# atx_power_control.net
KiCad netlist of a schematic drawn in EAGLE
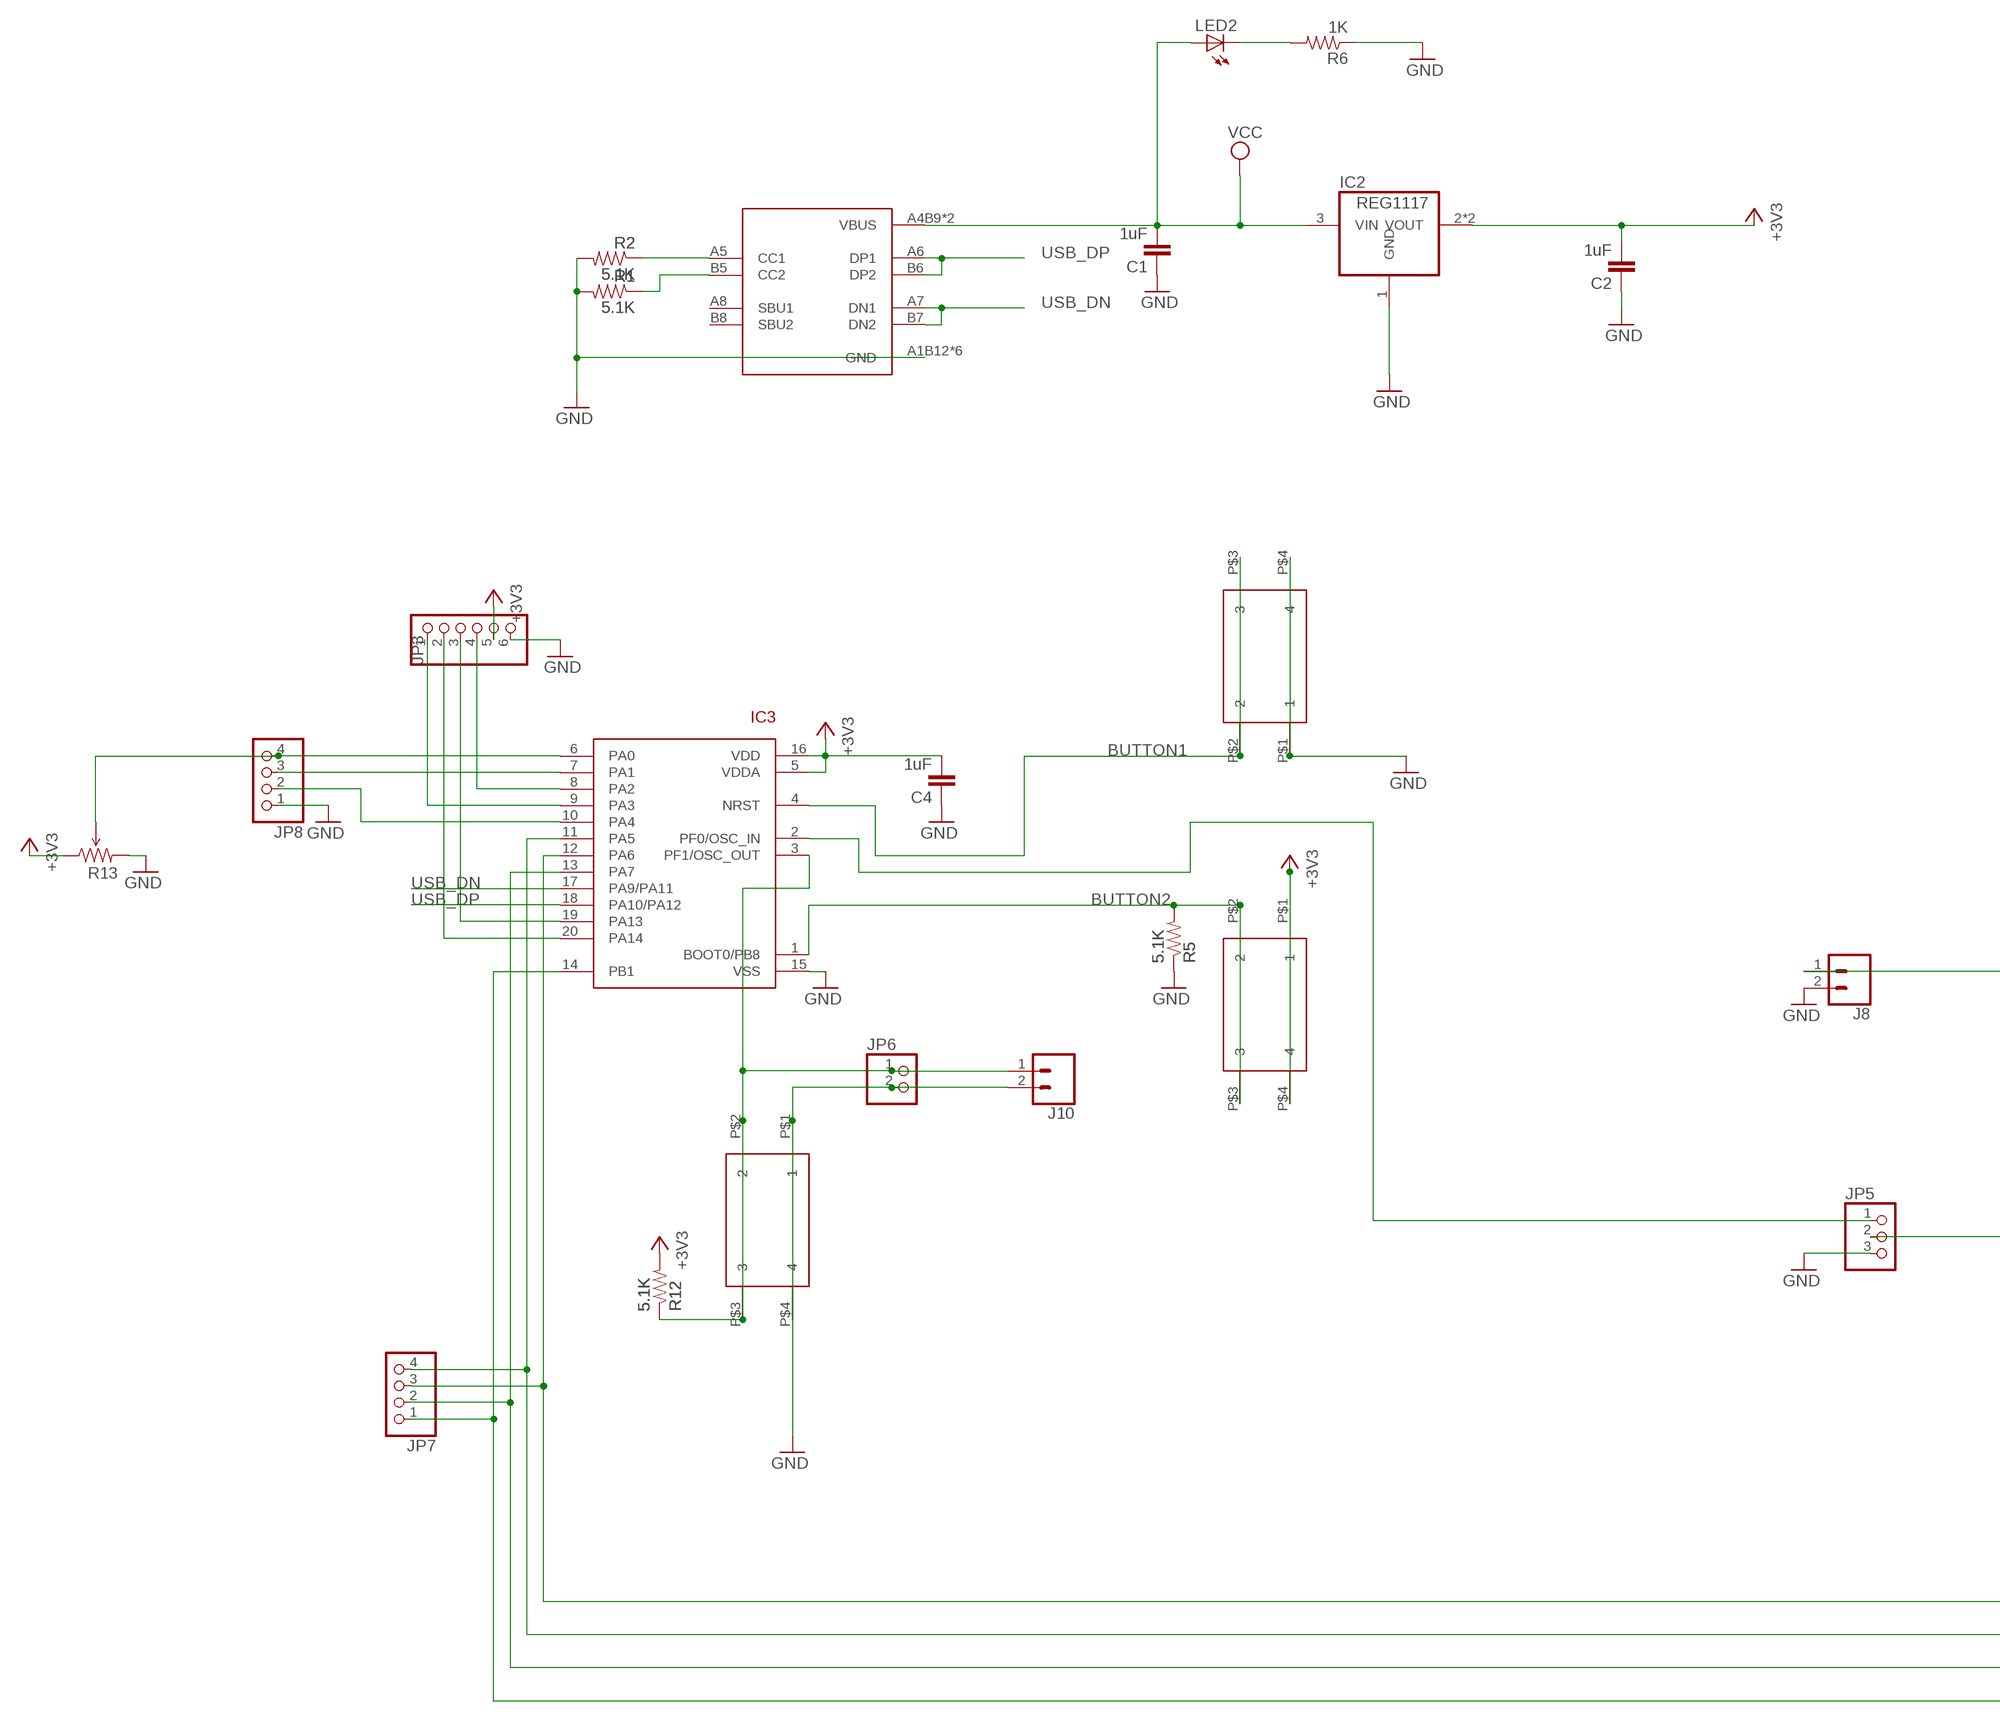
[diagram p0: schematic, sheet 1, part 1 of 2]
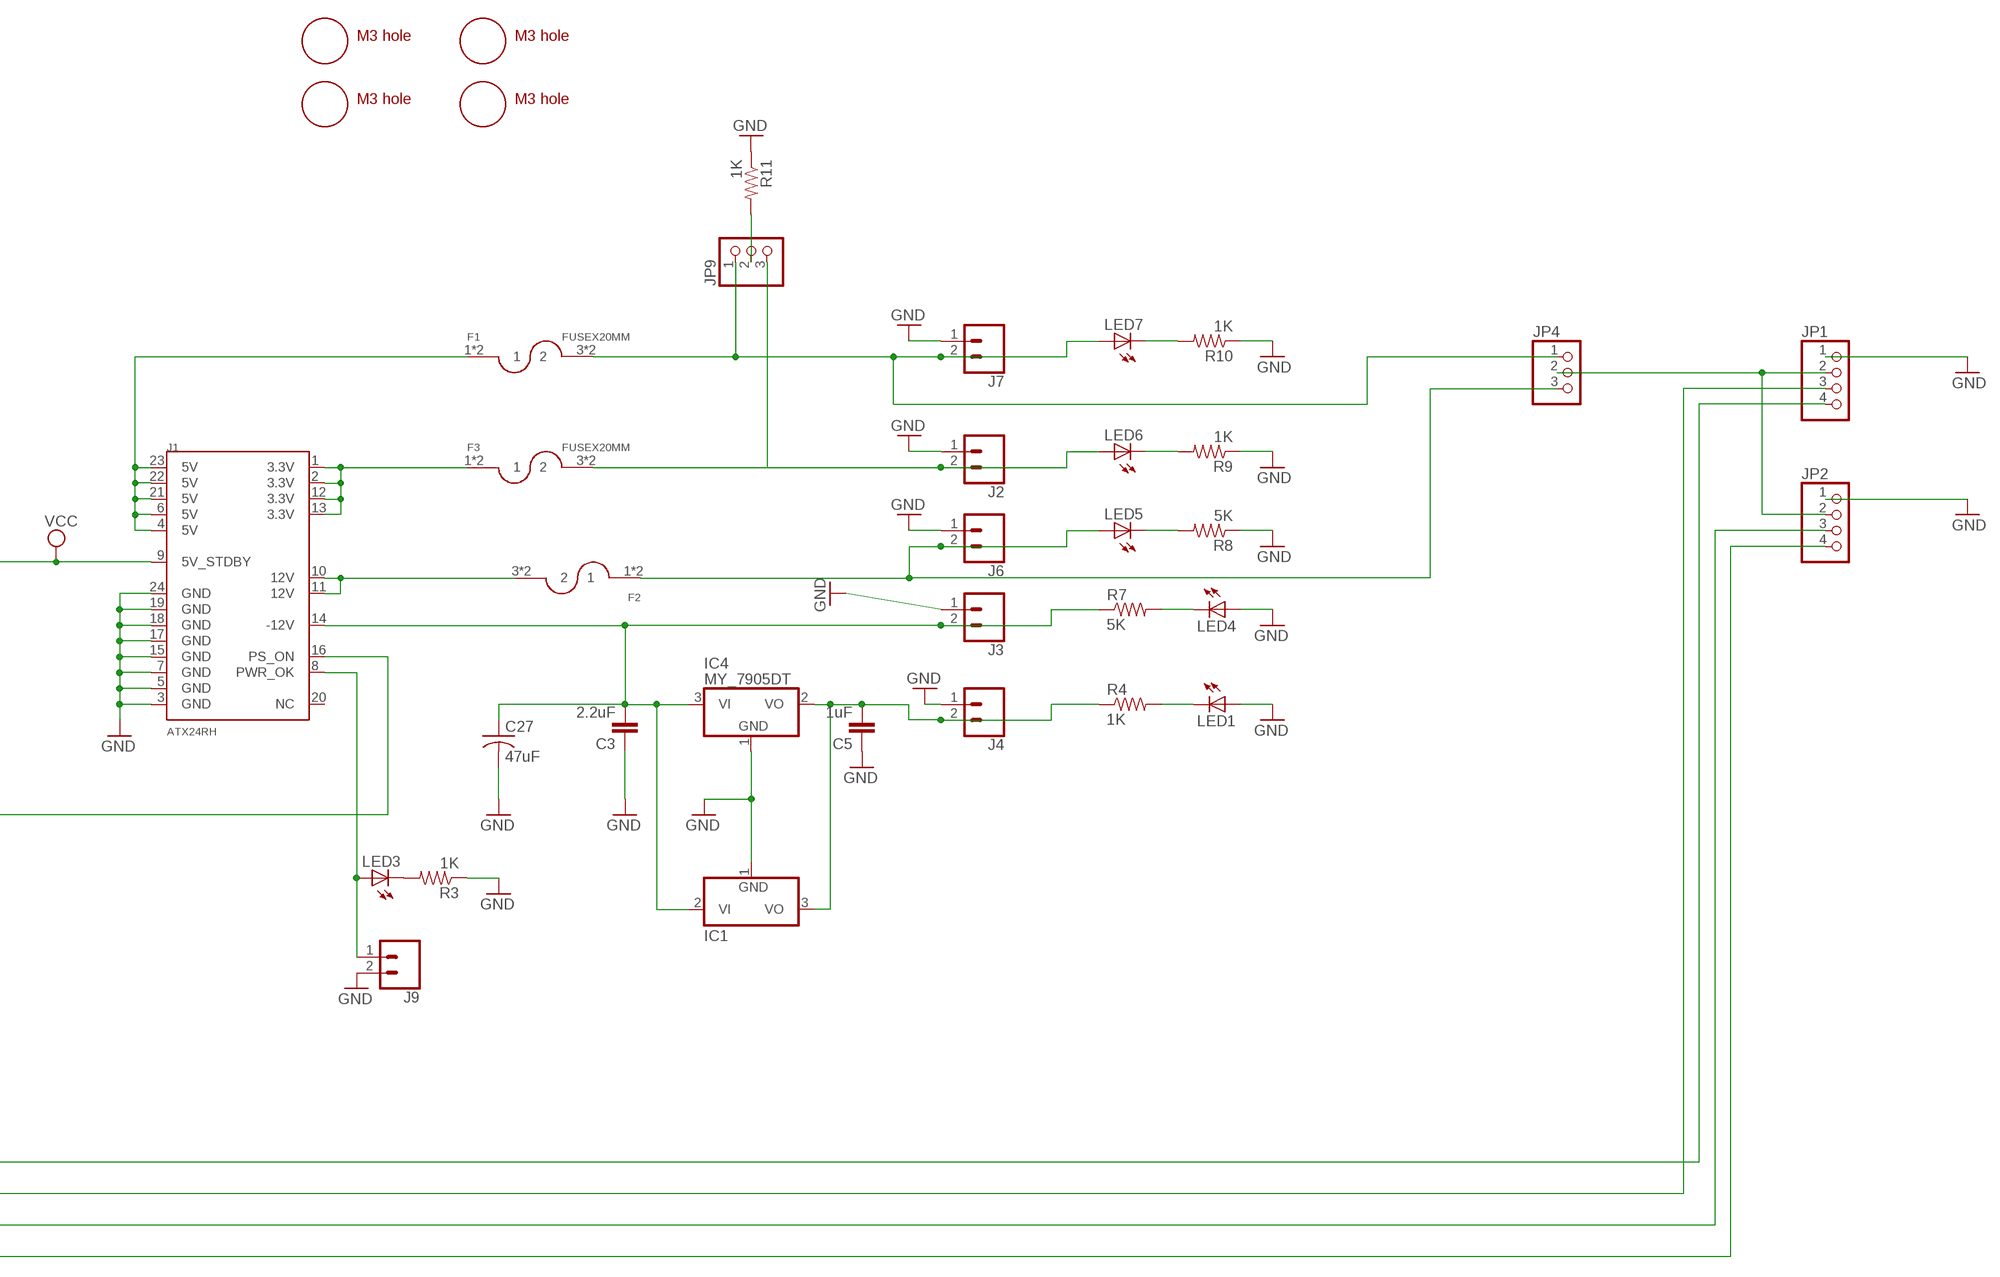
[diagram p1: schematic, sheet 1, part 2 of 2]

(export (version "E")
  (design (tool "Eeschema 10.0.6"))
  (components
    (comp (ref "C1")
      (value "1uF")
      (footprint "eagle-import:0805@1")
      (libsource (lib "eagle-import") (part "CAP0805"))
    )
    (comp (ref "C2")
      (value "1uF")
      (footprint "eagle-import:0805@1")
      (libsource (lib "eagle-import") (part "CAP0805"))
    )
    (comp (ref "C3")
      (value "2.2uF")
      (footprint "eagle-import:0805@1")
      (libsource (lib "eagle-import") (part "CAP0805"))
    )
    (comp (ref "C4")
      (value "1uF")
      (footprint "eagle-import:0805@1")
      (libsource (lib "eagle-import") (part "CAP0805"))
    )
    (comp (ref "C5")
      (value "1uF")
      (footprint "eagle-import:0805@1")
      (libsource (lib "eagle-import") (part "CAP0805"))
    )
    (comp (ref "C27")
      (value "47uF")
      (footprint "eagle-import:C1210")
      (libsource (lib "eagle-import") (part "C-USC1210"))
    )
    (comp (ref "F1")
      (value "FUSEX20MM")
      (footprint "eagle-import:FUSE_5MM")
      (libsource (lib "eagle-import") (part "FUSEX20MM"))
    )
    (comp (ref "F2")
      (value "FUSEX20MM")
      (footprint "eagle-import:FUSE_5MM")
      (libsource (lib "eagle-import") (part "FUSEX20MM"))
    )
    (comp (ref "F3")
      (value "FUSEX20MM")
      (footprint "eagle-import:FUSE_5MM")
      (libsource (lib "eagle-import") (part "FUSEX20MM"))
    )
    (comp (ref "IC1")
      (value "7905T")
      (footprint "eagle-import:TO220H")
      (libsource (lib "eagle-import") (part "79T05"))
    )
    (comp (ref "IC2")
      (value "REG1117")
      (footprint "eagle-import:SOT223")
      (libsource (lib "eagle-import") (part "REG1117"))
    )
    (comp (ref "IC3")
      (value "STM32F042F4")
      (footprint "eagle-import:TSSOP20")
      (libsource (lib "eagle-import") (part "STM32F042F4"))
    )
    (comp (ref "IC4")
      (value "MY_7905DT")
      (footprint "eagle-import:ADAFRUIT_TO252")
      (libsource (lib "eagle-import") (part "MY_7905DT"))
    )
    (comp (ref "J1")
      (value "ATX24RH")
      (footprint "eagle-import:ATX24_RIGHT_ANGLE")
      (libsource (lib "eagle-import") (part "ATX24RH"))
    )
    (comp (ref "J2")
      (value "CONN_023.5MM")
      (footprint "eagle-import:SCREWTERMINAL-3.5MM-2")
      (libsource (lib "eagle-import") (part "CONN_023.5MM"))
    )
    (comp (ref "J3")
      (value "CONN_023.5MM")
      (footprint "eagle-import:SCREWTERMINAL-3.5MM-2")
      (libsource (lib "eagle-import") (part "CONN_023.5MM"))
    )
    (comp (ref "J4")
      (value "CONN_023.5MM")
      (footprint "eagle-import:SCREWTERMINAL-3.5MM-2")
      (libsource (lib "eagle-import") (part "CONN_023.5MM"))
    )
    (comp (ref "J6")
      (value "CONN_023.5MM")
      (footprint "eagle-import:SCREWTERMINAL-3.5MM-2")
      (libsource (lib "eagle-import") (part "CONN_023.5MM"))
    )
    (comp (ref "J7")
      (value "CONN_023.5MM")
      (footprint "eagle-import:SCREWTERMINAL-3.5MM-2")
      (libsource (lib "eagle-import") (part "CONN_023.5MM"))
    )
    (comp (ref "J8")
      (value "CONN_023.5MM")
      (footprint "eagle-import:SCREWTERMINAL-3.5MM-2")
      (libsource (lib "eagle-import") (part "CONN_023.5MM"))
    )
    (comp (ref "J9")
      (value "CONN_023.5MM")
      (footprint "eagle-import:SCREWTERMINAL-3.5MM-2")
      (libsource (lib "eagle-import") (part "CONN_023.5MM"))
    )
    (comp (ref "J10")
      (value "CONN_023.5MM")
      (footprint "eagle-import:SCREWTERMINAL-3.5MM-2")
      (libsource (lib "eagle-import") (part "CONN_023.5MM"))
    )
    (comp (ref "JP1")
      (value "PINHD-1X4")
      (footprint "eagle-import:1X04")
      (libsource (lib "eagle-import") (part "PINHD-1X4"))
    )
    (comp (ref "JP2")
      (value "PINHD-1X4")
      (footprint "eagle-import:1X04")
      (libsource (lib "eagle-import") (part "PINHD-1X4"))
    )
    (comp (ref "JP3")
      (value "PINHD-1X6")
      (footprint "eagle-import:1X06")
      (libsource (lib "eagle-import") (part "PINHD-1X6"))
    )
    (comp (ref "JP4")
      (value "PINHD-1X3")
      (footprint "eagle-import:1X03")
      (libsource (lib "eagle-import") (part "PINHD-1X3"))
    )
    (comp (ref "JP5")
      (value "PINHD-1X3")
      (footprint "eagle-import:1X03")
      (libsource (lib "eagle-import") (part "PINHD-1X3"))
    )
    (comp (ref "JP6")
      (value "PINHD-1X2")
      (footprint "eagle-import:1X02")
      (libsource (lib "eagle-import") (part "PINHD-1X2"))
    )
    (comp (ref "JP7")
      (value "PINHD-1X4")
      (footprint "eagle-import:1X04")
      (libsource (lib "eagle-import") (part "PINHD-1X4"))
    )
    (comp (ref "JP8")
      (value "PINHD-1X4")
      (footprint "eagle-import:1X04")
      (libsource (lib "eagle-import") (part "PINHD-1X4"))
    )
    (comp (ref "JP9")
      (value "PINHD-1X3")
      (footprint "eagle-import:1X03")
      (libsource (lib "eagle-import") (part "PINHD-1X3"))
    )
    (comp (ref "LED1")
      (value "LEDCHIP-LED0805")
      (footprint "eagle-import:CHIP-LED0805")
      (libsource (lib "eagle-import") (part "LEDCHIP-LED0805"))
    )
    (comp (ref "LED2")
      (value "LEDCHIP-LED0805")
      (footprint "eagle-import:CHIP-LED0805")
      (libsource (lib "eagle-import") (part "LEDCHIP-LED0805"))
    )
    (comp (ref "LED3")
      (value "LEDCHIP-LED0805")
      (footprint "eagle-import:CHIP-LED0805")
      (libsource (lib "eagle-import") (part "LEDCHIP-LED0805"))
    )
    (comp (ref "LED4")
      (value "LEDCHIP-LED0805")
      (footprint "eagle-import:CHIP-LED0805")
      (libsource (lib "eagle-import") (part "LEDCHIP-LED0805"))
    )
    (comp (ref "LED5")
      (value "LEDCHIP-LED0805")
      (footprint "eagle-import:CHIP-LED0805")
      (libsource (lib "eagle-import") (part "LEDCHIP-LED0805"))
    )
    (comp (ref "LED6")
      (value "LEDCHIP-LED0805")
      (footprint "eagle-import:CHIP-LED0805")
      (libsource (lib "eagle-import") (part "LEDCHIP-LED0805"))
    )
    (comp (ref "LED7")
      (value "LEDCHIP-LED0805")
      (footprint "eagle-import:CHIP-LED0805")
      (libsource (lib "eagle-import") (part "LEDCHIP-LED0805"))
    )
    (comp (ref "R1")
      (value "5.1K")
      (footprint "eagle-import:0805")
      (libsource (lib "eagle-import") (part "joyAnalog_RESISTOR0805-RES"))
    )
    (comp (ref "R2")
      (value "5.1K")
      (footprint "eagle-import:0805")
      (libsource (lib "eagle-import") (part "joyAnalog_RESISTOR0805-RES"))
    )
    (comp (ref "R3")
      (value "1K")
      (footprint "eagle-import:0805")
      (libsource (lib "eagle-import") (part "RESISTOR0805-RES"))
    )
    (comp (ref "R4")
      (value "1K")
      (footprint "eagle-import:0805")
      (libsource (lib "eagle-import") (part "RESISTOR0805-RES"))
    )
    (comp (ref "R5")
      (value "5.1K")
      (footprint "eagle-import:0805")
      (libsource (lib "eagle-import") (part "joyAnalog_RESISTOR0805-RES"))
    )
    (comp (ref "R6")
      (value "1K")
      (footprint "eagle-import:0805")
      (libsource (lib "eagle-import") (part "RESISTOR0805-RES"))
    )
    (comp (ref "R7")
      (value "5K")
      (footprint "eagle-import:0805")
      (libsource (lib "eagle-import") (part "RESISTOR0805-RES"))
    )
    (comp (ref "R8")
      (value "5K")
      (footprint "eagle-import:0805")
      (libsource (lib "eagle-import") (part "RESISTOR0805-RES"))
    )
    (comp (ref "R9")
      (value "1K")
      (footprint "eagle-import:0805")
      (libsource (lib "eagle-import") (part "RESISTOR0805-RES"))
    )
    (comp (ref "R10")
      (value "1K")
      (footprint "eagle-import:0805")
      (libsource (lib "eagle-import") (part "RESISTOR0805-RES"))
    )
    (comp (ref "R11")
      (value "1K")
      (footprint "eagle-import:0805")
      (libsource (lib "eagle-import") (part "RESISTOR0805-RES"))
    )
    (comp (ref "R12")
      (value "5.1K")
      (footprint "eagle-import:0805")
      (libsource (lib "eagle-import") (part "joyAnalog_RESISTOR0805-RES"))
    )
    (comp (ref "R13")
      (value "TRIMPOTPTH")
      (footprint "eagle-import:TRIM_POT_PTH")
      (libsource (lib "eagle-import") (part "TRIMPOTPTH"))
    )
    (comp (ref "SW1")
      (value "324_SW")
      (footprint "eagle-import:342_SWICH_FOOT")
      (libsource (lib "eagle-import") (part "324_SW"))
    )
    (comp (ref "SW3")
      (value "324_SW")
      (footprint "eagle-import:342_SWICH_FOOT")
      (libsource (lib "eagle-import") (part "324_SW"))
    )
    (comp (ref "SW4")
      (value "324_SW")
      (footprint "eagle-import:342_SWICH_FOOT")
      (libsource (lib "eagle-import") (part "324_SW"))
    )
    (comp (ref "U$1")
      (value "M3_MOUNTING_HOLE")
      (footprint "eagle-import:M3_MOUNTING_HOLE_PACK")
      (libsource (lib "eagle-import") (part "M3_MOUNTING_HOLE"))
    )
    (comp (ref "U$2")
      (value "M3_MOUNTING_HOLE")
      (footprint "eagle-import:M3_MOUNTING_HOLE_PACK")
      (libsource (lib "eagle-import") (part "M3_MOUNTING_HOLE"))
    )
    (comp (ref "U$3")
      (value "M3_MOUNTING_HOLE")
      (footprint "eagle-import:M3_MOUNTING_HOLE_PACK")
      (libsource (lib "eagle-import") (part "M3_MOUNTING_HOLE"))
    )
    (comp (ref "U$10")
      (value "M3_MOUNTING_HOLE")
      (footprint "eagle-import:M3_MOUNTING_HOLE_PACK")
      (libsource (lib "eagle-import") (part "M3_MOUNTING_HOLE"))
    )
    (comp (ref "U2")
      (value "USBC_16P")
      (footprint "eagle-import:USBC_16P_FOOT")
      (libsource (lib "eagle-import") (part "USBC_16P"))
    )
  )
  (nets
    (net (code "1") (name "+3V3") (class "Default")
      (node (ref "C2") (pin "2") (pinfunction "2_2") (pintype "passive"))
      (node (ref "C4") (pin "2") (pinfunction "2_2") (pintype "passive"))
      (node (ref "IC2") (pin "2") (pinfunction "VOUT_2") (pintype "output"))
      (node (ref "IC2") (pin "4") (pinfunction "VOUT_4") (pintype "output"))
      (node (ref "IC3") (pin "16") (pinfunction "VDD_16") (pintype "bidirectional"))
      (node (ref "IC3") (pin "5") (pinfunction "VDDA_5") (pintype "bidirectional"))
      (node (ref "JP3") (pin "5") (pinfunction "5_5") (pintype "passive"))
      (node (ref "R12") (pin "2") (pinfunction "2_2") (pintype "passive"))
      (node (ref "R13") (pin "1") (pinfunction "CCW_1") (pintype "passive"))
      (node (ref "SW4") (pin "P$1") (pinfunction "1_P$1") (pintype "bidirectional"))
      (node (ref "SW4") (pin "P$4") (pinfunction "4_P$4") (pintype "bidirectional"))
    )
    (net (code "2") (name "/BUTTON1") (class "Default")
      (node (ref "IC3") (pin "4") (pinfunction "NRST_4") (pintype "bidirectional"))
      (node (ref "SW3") (pin "P$2") (pinfunction "2_P$2") (pintype "bidirectional"))
      (node (ref "SW3") (pin "P$3") (pinfunction "3_P$3") (pintype "bidirectional"))
    )
    (net (code "3") (name "/BUTTON2") (class "Default")
      (node (ref "IC3") (pin "1") (pinfunction "BOOT0/PB8_1") (pintype "bidirectional"))
      (node (ref "R5") (pin "2") (pinfunction "2_2") (pintype "passive"))
      (node (ref "SW4") (pin "P$2") (pinfunction "2_P$2") (pintype "bidirectional"))
      (node (ref "SW4") (pin "P$3") (pinfunction "3_P$3") (pintype "bidirectional"))
    )
    (net (code "4") (name "/USB_DN") (class "Default")
      (node (ref "IC3") (pin "17") (pinfunction "PA9/PA11_17") (pintype "bidirectional"))
      (node (ref "U2") (pin "A7") (pinfunction "DN1_A7") (pintype "bidirectional"))
      (node (ref "U2") (pin "B7") (pinfunction "DN2_B7") (pintype "bidirectional"))
    )
    (net (code "5") (name "/USB_DP") (class "Default")
      (node (ref "IC3") (pin "18") (pinfunction "PA10/PA12_18") (pintype "bidirectional"))
      (node (ref "U2") (pin "A6") (pinfunction "DP1_A6") (pintype "bidirectional"))
      (node (ref "U2") (pin "B6") (pinfunction "DP2_B6") (pintype "bidirectional"))
    )
    (net (code "6") (name "GND") (class "Default")
      (node (ref "C1") (pin "1") (pinfunction "1_1") (pintype "passive"))
      (node (ref "C2") (pin "1") (pinfunction "1_1") (pintype "passive"))
      (node (ref "C27") (pin "2") (pinfunction "2_2") (pintype "passive"))
      (node (ref "C3") (pin "1") (pinfunction "1_1") (pintype "passive"))
      (node (ref "C4") (pin "1") (pinfunction "1_1") (pintype "passive"))
      (node (ref "C5") (pin "1") (pinfunction "1_1") (pintype "passive"))
      (node (ref "IC1") (pin "1") (pinfunction "GND_1") (pintype "passive"))
      (node (ref "IC2") (pin "1") (pinfunction "GND_1") (pintype "power_in"))
      (node (ref "IC3") (pin "15") (pinfunction "VSS_15") (pintype "bidirectional"))
      (node (ref "IC4") (pin "1") (pinfunction "GND_1") (pintype "passive"))
      (node (ref "J1") (pin "15") (pinfunction "GND_15") (pintype "bidirectional"))
      (node (ref "J1") (pin "17") (pinfunction "GND_17") (pintype "bidirectional"))
      (node (ref "J1") (pin "18") (pinfunction "GND_18") (pintype "bidirectional"))
      (node (ref "J1") (pin "19") (pinfunction "GND_19") (pintype "bidirectional"))
      (node (ref "J1") (pin "24") (pinfunction "GND_24") (pintype "bidirectional"))
      (node (ref "J1") (pin "3") (pinfunction "GND_3") (pintype "bidirectional"))
      (node (ref "J1") (pin "5") (pinfunction "GND_5") (pintype "bidirectional"))
      (node (ref "J1") (pin "7") (pinfunction "GND_7") (pintype "bidirectional"))
      (node (ref "J10") (pin "2") (pinfunction "2_2") (pintype "passive"))
      (node (ref "J2") (pin "1") (pinfunction "1_1") (pintype "passive"))
      (node (ref "J3") (pin "1") (pinfunction "1_1") (pintype "passive"))
      (node (ref "J4") (pin "1") (pinfunction "1_1") (pintype "passive"))
      (node (ref "J6") (pin "1") (pinfunction "1_1") (pintype "passive"))
      (node (ref "J7") (pin "1") (pinfunction "1_1") (pintype "passive"))
      (node (ref "J8") (pin "2") (pinfunction "2_2") (pintype "passive"))
      (node (ref "J9") (pin "2") (pinfunction "2_2") (pintype "passive"))
      (node (ref "JP1") (pin "1") (pinfunction "1_1") (pintype "passive"))
      (node (ref "JP2") (pin "1") (pinfunction "1_1") (pintype "passive"))
      (node (ref "JP3") (pin "6") (pinfunction "6_6") (pintype "passive"))
      (node (ref "JP5") (pin "3") (pinfunction "3_3") (pintype "passive"))
      (node (ref "JP6") (pin "2") (pinfunction "2_2") (pintype "passive"))
      (node (ref "JP8") (pin "1") (pinfunction "1_1") (pintype "passive"))
      (node (ref "LED1") (pin "A") (pinfunction "A_A") (pintype "passive"))
      (node (ref "LED4") (pin "A") (pinfunction "A_A") (pintype "passive"))
      (node (ref "R1") (pin "2") (pinfunction "2_2") (pintype "passive"))
      (node (ref "R10") (pin "1") (pinfunction "1_1") (pintype "passive"))
      (node (ref "R11") (pin "1") (pinfunction "1_1") (pintype "passive"))
      (node (ref "R13") (pin "3") (pinfunction "CW_3") (pintype "passive"))
      (node (ref "R2") (pin "2") (pinfunction "2_2") (pintype "passive"))
      (node (ref "R3") (pin "1") (pinfunction "1_1") (pintype "passive"))
      (node (ref "R5") (pin "1") (pinfunction "1_1") (pintype "passive"))
      (node (ref "R6") (pin "1") (pinfunction "1_1") (pintype "passive"))
      (node (ref "R8") (pin "1") (pinfunction "1_1") (pintype "passive"))
      (node (ref "R9") (pin "1") (pinfunction "1_1") (pintype "passive"))
      (node (ref "SW1") (pin "P$1") (pinfunction "1_P$1") (pintype "bidirectional"))
      (node (ref "SW1") (pin "P$4") (pinfunction "4_P$4") (pintype "bidirectional"))
      (node (ref "SW3") (pin "P$1") (pinfunction "1_P$1") (pintype "bidirectional"))
      (node (ref "SW3") (pin "P$4") (pinfunction "4_P$4") (pintype "bidirectional"))
      (node (ref "U2") (pin "A1B12") (pinfunction "GND_A1B12") (pintype "bidirectional"))
      (node (ref "U2") (pin "B11A12") (pinfunction "GND_B11A12") (pintype "bidirectional"))
      (node (ref "U2") (pin "P$13") (pinfunction "GND_P$13") (pintype "bidirectional"))
      (node (ref "U2") (pin "P$14") (pinfunction "GND_P$14") (pintype "bidirectional"))
      (node (ref "U2") (pin "P$15") (pinfunction "GND_P$15") (pintype "bidirectional"))
      (node (ref "U2") (pin "P$16") (pinfunction "GND_P$16") (pintype "bidirectional"))
    )
    (net (code "7") (name "Net-(F1-1-Pad2)") (class "Default")
      (node (ref "F1") (pin "1") (pinfunction "1_1") (pintype "bidirectional"))
      (node (ref "F1") (pin "2") (pinfunction "1_2") (pintype "bidirectional"))
      (node (ref "J1") (pin "21") (pinfunction "5V_21") (pintype "bidirectional"))
      (node (ref "J1") (pin "22") (pinfunction "5V_22") (pintype "bidirectional"))
      (node (ref "J1") (pin "23") (pinfunction "5V_23") (pintype "bidirectional"))
      (node (ref "J1") (pin "4") (pinfunction "5V_4") (pintype "bidirectional"))
      (node (ref "J1") (pin "6") (pinfunction "5V_6") (pintype "bidirectional"))
    )
    (net (code "8") (name "Net-(F1-2-Pad3)") (class "Default")
      (node (ref "F1") (pin "3") (pinfunction "2_3") (pintype "bidirectional"))
      (node (ref "F1") (pin "4") (pinfunction "2_4") (pintype "bidirectional"))
      (node (ref "J7") (pin "2") (pinfunction "2_2") (pintype "passive"))
      (node (ref "JP4") (pin "1") (pinfunction "1_1") (pintype "passive"))
      (node (ref "JP9") (pin "1") (pinfunction "1_1") (pintype "passive"))
      (node (ref "LED7") (pin "A") (pinfunction "A_A") (pintype "passive"))
    )
    (net (code "9") (name "Net-(F2-1-Pad2)") (class "Default")
      (node (ref "F2") (pin "1") (pinfunction "1_1") (pintype "bidirectional"))
      (node (ref "F2") (pin "2") (pinfunction "1_2") (pintype "bidirectional"))
      (node (ref "J6") (pin "2") (pinfunction "2_2") (pintype "passive"))
      (node (ref "JP4") (pin "3") (pinfunction "3_3") (pintype "passive"))
      (node (ref "LED5") (pin "A") (pinfunction "A_A") (pintype "passive"))
    )
    (net (code "10") (name "Net-(F2-2-Pad3)") (class "Default")
      (node (ref "F2") (pin "3") (pinfunction "2_3") (pintype "bidirectional"))
      (node (ref "F2") (pin "4") (pinfunction "2_4") (pintype "bidirectional"))
      (node (ref "J1") (pin "10") (pinfunction "12V_10") (pintype "bidirectional"))
      (node (ref "J1") (pin "11") (pinfunction "12V_11") (pintype "bidirectional"))
    )
    (net (code "11") (name "Net-(F3-1-Pad2)") (class "Default")
      (node (ref "F3") (pin "1") (pinfunction "1_1") (pintype "bidirectional"))
      (node (ref "F3") (pin "2") (pinfunction "1_2") (pintype "bidirectional"))
      (node (ref "J1") (pin "1") (pinfunction "3.3V_1") (pintype "bidirectional"))
      (node (ref "J1") (pin "12") (pinfunction "3.3V_12") (pintype "bidirectional"))
      (node (ref "J1") (pin "13") (pinfunction "3.3V_13") (pintype "bidirectional"))
      (node (ref "J1") (pin "2") (pinfunction "3.3V_2") (pintype "bidirectional"))
    )
    (net (code "12") (name "Net-(F3-2-Pad3)") (class "Default")
      (node (ref "F3") (pin "3") (pinfunction "2_3") (pintype "bidirectional"))
      (node (ref "F3") (pin "4") (pinfunction "2_4") (pintype "bidirectional"))
      (node (ref "J2") (pin "2") (pinfunction "2_2") (pintype "passive"))
      (node (ref "JP9") (pin "3") (pinfunction "3_3") (pintype "passive"))
      (node (ref "LED6") (pin "A") (pinfunction "A_A") (pintype "passive"))
    )
    (net (code "13") (name "Net-(IC1-VI)") (class "Default")
      (node (ref "C27") (pin "1") (pinfunction "1_1") (pintype "passive"))
      (node (ref "C3") (pin "2") (pinfunction "2_2") (pintype "passive"))
      (node (ref "IC1") (pin "2") (pinfunction "VI_2") (pintype "input"))
      (node (ref "IC4") (pin "3") (pinfunction "VI_3") (pintype "input"))
      (node (ref "J1") (pin "14") (pinfunction "-12V_14") (pintype "bidirectional"))
      (node (ref "J3") (pin "2") (pinfunction "2_2") (pintype "passive"))
      (node (ref "R7") (pin "1") (pinfunction "1_1") (pintype "passive"))
    )
    (net (code "14") (name "Net-(IC1-VO)") (class "Default")
      (node (ref "C5") (pin "2") (pinfunction "2_2") (pintype "passive"))
      (node (ref "IC1") (pin "3") (pinfunction "VO_3") (pintype "passive"))
      (node (ref "IC4") (pin "2") (pinfunction "VO_2") (pintype "passive"))
      (node (ref "J4") (pin "2") (pinfunction "2_2") (pintype "passive"))
      (node (ref "R4") (pin "1") (pinfunction "1_1") (pintype "passive"))
    )
    (net (code "15") (name "Net-(IC3-PA0)") (class "Default")
      (node (ref "IC3") (pin "6") (pinfunction "PA0_6") (pintype "bidirectional"))
      (node (ref "JP8") (pin "4") (pinfunction "4_4") (pintype "passive"))
      (node (ref "R13") (pin "2") (pinfunction "WIPER_2") (pintype "passive"))
    )
    (net (code "16") (name "Net-(IC3-PA1)") (class "Default")
      (node (ref "IC3") (pin "7") (pinfunction "PA1_7") (pintype "bidirectional"))
      (node (ref "JP8") (pin "3") (pinfunction "3_3") (pintype "passive"))
    )
    (net (code "17") (name "Net-(IC3-PA2)") (class "Default")
      (node (ref "IC3") (pin "8") (pinfunction "PA2_8") (pintype "bidirectional"))
      (node (ref "JP3") (pin "4") (pinfunction "4_4") (pintype "passive"))
    )
    (net (code "18") (name "Net-(IC3-PA3)") (class "Default")
      (node (ref "IC3") (pin "9") (pinfunction "PA3_9") (pintype "bidirectional"))
      (node (ref "JP3") (pin "1") (pinfunction "1_1") (pintype "passive"))
    )
    (net (code "19") (name "Net-(IC3-PA4)") (class "Default")
      (node (ref "IC3") (pin "10") (pinfunction "PA4_10") (pintype "bidirectional"))
      (node (ref "JP8") (pin "2") (pinfunction "2_2") (pintype "passive"))
    )
    (net (code "20") (name "Net-(IC3-PA5)") (class "Default")
      (node (ref "IC3") (pin "11") (pinfunction "PA5_11") (pintype "bidirectional"))
      (node (ref "JP1") (pin "3") (pinfunction "3_3") (pintype "passive"))
      (node (ref "JP7") (pin "4") (pinfunction "4_4") (pintype "passive"))
    )
    (net (code "21") (name "Net-(IC3-PA6)") (class "Default")
      (node (ref "IC3") (pin "12") (pinfunction "PA6_12") (pintype "bidirectional"))
      (node (ref "JP1") (pin "4") (pinfunction "4_4") (pintype "passive"))
      (node (ref "JP7") (pin "3") (pinfunction "3_3") (pintype "passive"))
    )
    (net (code "22") (name "Net-(IC3-PA7)") (class "Default")
      (node (ref "IC3") (pin "13") (pinfunction "PA7_13") (pintype "bidirectional"))
      (node (ref "JP2") (pin "3") (pinfunction "3_3") (pintype "passive"))
      (node (ref "JP7") (pin "2") (pinfunction "2_2") (pintype "passive"))
    )
    (net (code "23") (name "Net-(IC3-PA13)") (class "Default")
      (node (ref "IC3") (pin "19") (pinfunction "PA13_19") (pintype "bidirectional"))
      (node (ref "JP3") (pin "3") (pinfunction "3_3") (pintype "passive"))
    )
    (net (code "24") (name "Net-(IC3-PA14)") (class "Default")
      (node (ref "IC3") (pin "20") (pinfunction "PA14_20") (pintype "bidirectional"))
      (node (ref "JP3") (pin "2") (pinfunction "2_2") (pintype "passive"))
    )
    (net (code "25") (name "Net-(IC3-PB1)") (class "Default")
      (node (ref "IC3") (pin "14") (pinfunction "PB1_14") (pintype "bidirectional"))
      (node (ref "JP2") (pin "4") (pinfunction "4_4") (pintype "passive"))
      (node (ref "JP7") (pin "1") (pinfunction "1_1") (pintype "passive"))
    )
    (net (code "26") (name "Net-(IC3-PF0{slash}OSC_IN)") (class "Default")
      (node (ref "IC3") (pin "2") (pinfunction "PF0/OSC_IN_2") (pintype "bidirectional"))
      (node (ref "JP5") (pin "1") (pinfunction "1_1") (pintype "passive"))
    )
    (net (code "27") (name "Net-(IC3-PF1{slash}OSC_OUT)") (class "Default")
      (node (ref "IC3") (pin "3") (pinfunction "PF1/OSC_OUT_3") (pintype "bidirectional"))
      (node (ref "J10") (pin "1") (pinfunction "1_1") (pintype "passive"))
      (node (ref "JP6") (pin "1") (pinfunction "1_1") (pintype "passive"))
      (node (ref "R12") (pin "1") (pinfunction "1_1") (pintype "passive"))
      (node (ref "SW1") (pin "P$2") (pinfunction "2_P$2") (pintype "bidirectional"))
      (node (ref "SW1") (pin "P$3") (pinfunction "3_P$3") (pintype "bidirectional"))
    )
    (net (code "28") (name "Net-(J1-PS_ON)") (class "Default")
      (node (ref "J1") (pin "16") (pinfunction "PS_ON_16") (pintype "bidirectional"))
      (node (ref "JP5") (pin "2") (pinfunction "2_2") (pintype "passive"))
    )
    (net (code "29") (name "Net-(J1-PWR_OK)") (class "Default")
      (node (ref "J1") (pin "8") (pinfunction "PWR_OK_8") (pintype "bidirectional"))
      (node (ref "J9") (pin "1") (pinfunction "1_1") (pintype "passive"))
      (node (ref "LED3") (pin "A") (pinfunction "A_A") (pintype "passive"))
    )
    (net (code "30") (name "Net-(JP1-Pad2)") (class "Default")
      (node (ref "JP1") (pin "2") (pinfunction "2_2") (pintype "passive"))
      (node (ref "JP2") (pin "2") (pinfunction "2_2") (pintype "passive"))
      (node (ref "JP4") (pin "2") (pinfunction "2_2") (pintype "passive"))
    )
    (net (code "31") (name "Net-(JP9-Pad2)") (class "Default")
      (node (ref "JP9") (pin "2") (pinfunction "2_2") (pintype "passive"))
      (node (ref "R11") (pin "2") (pinfunction "2_2") (pintype "passive"))
    )
    (net (code "32") (name "Net-(LED1-PadC)") (class "Default")
      (node (ref "LED1") (pin "C") (pinfunction "C_C") (pintype "passive"))
      (node (ref "R4") (pin "2") (pinfunction "2_2") (pintype "passive"))
    )
    (net (code "33") (name "Net-(LED2-PadC)") (class "Default")
      (node (ref "LED2") (pin "C") (pinfunction "C_C") (pintype "passive"))
      (node (ref "R6") (pin "2") (pinfunction "2_2") (pintype "passive"))
    )
    (net (code "34") (name "Net-(LED3-PadC)") (class "Default")
      (node (ref "LED3") (pin "C") (pinfunction "C_C") (pintype "passive"))
      (node (ref "R3") (pin "2") (pinfunction "2_2") (pintype "passive"))
    )
    (net (code "35") (name "Net-(LED4-PadC)") (class "Default")
      (node (ref "LED4") (pin "C") (pinfunction "C_C") (pintype "passive"))
      (node (ref "R7") (pin "2") (pinfunction "2_2") (pintype "passive"))
    )
    (net (code "36") (name "Net-(LED5-PadC)") (class "Default")
      (node (ref "LED5") (pin "C") (pinfunction "C_C") (pintype "passive"))
      (node (ref "R8") (pin "2") (pinfunction "2_2") (pintype "passive"))
    )
    (net (code "37") (name "Net-(LED6-PadC)") (class "Default")
      (node (ref "LED6") (pin "C") (pinfunction "C_C") (pintype "passive"))
      (node (ref "R9") (pin "2") (pinfunction "2_2") (pintype "passive"))
    )
    (net (code "38") (name "Net-(LED7-PadC)") (class "Default")
      (node (ref "LED7") (pin "C") (pinfunction "C_C") (pintype "passive"))
      (node (ref "R10") (pin "2") (pinfunction "2_2") (pintype "passive"))
    )
    (net (code "39") (name "Net-(U2-CC1)") (class "Default")
      (node (ref "R2") (pin "1") (pinfunction "1_1") (pintype "passive"))
      (node (ref "U2") (pin "A5") (pinfunction "CC1_A5") (pintype "bidirectional"))
    )
    (net (code "40") (name "Net-(U2-CC2)") (class "Default")
      (node (ref "R1") (pin "1") (pinfunction "1_1") (pintype "passive"))
      (node (ref "U2") (pin "B5") (pinfunction "CC2_B5") (pintype "bidirectional"))
    )
    (net (code "41") (name "VCC") (class "Default")
      (node (ref "C1") (pin "2") (pinfunction "2_2") (pintype "passive"))
      (node (ref "IC2") (pin "3") (pinfunction "VIN_3") (pintype "input"))
      (node (ref "J1") (pin "9") (pinfunction "5V_STDBY_9") (pintype "bidirectional"))
      (node (ref "J8") (pin "1") (pinfunction "1_1") (pintype "passive"))
      (node (ref "LED2") (pin "A") (pinfunction "A_A") (pintype "passive"))
      (node (ref "U2") (pin "A4B9") (pinfunction "VBUS_A4B9") (pintype "bidirectional"))
      (node (ref "U2") (pin "B4A9") (pinfunction "VBUS_B4A9") (pintype "bidirectional"))
    )
    (net (code "42") (name "unconnected-(J1-NC-Pad20)") (class "Default")
      (node (ref "J1") (pin "20") (pinfunction "NC_20") (pintype "bidirectional"))
    )
    (net (code "43") (name "unconnected-(U2-SBU1-PadA8)") (class "Default")
      (node (ref "U2") (pin "A8") (pinfunction "SBU1_A8") (pintype "bidirectional"))
    )
    (net (code "44") (name "unconnected-(U2-SBU2-PadB8)") (class "Default")
      (node (ref "U2") (pin "B8") (pinfunction "SBU2_B8") (pintype "bidirectional"))
    )
  )
)
